# Zocalo-mcp2515.net
KiCad netlist of a schematic drawn in EAGLE
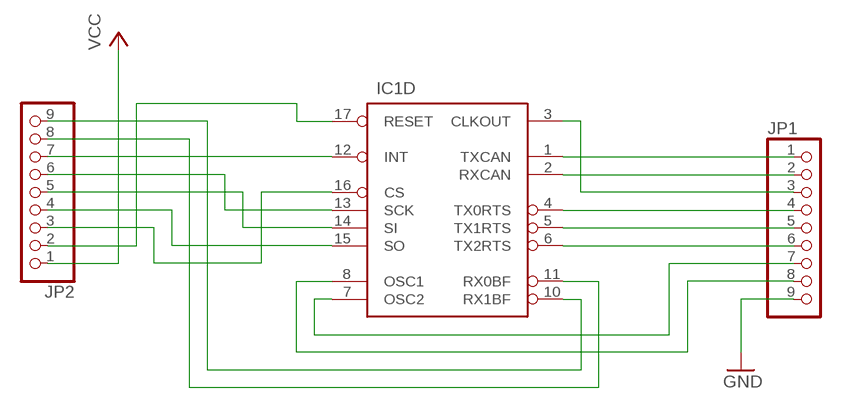
[diagram p0: schematic, sheet 1]

(export (version "E")
  (design (tool "Eeschema 10.0.6"))
  (components
    (comp (ref "IC1")
      (value "MCP2515SO")
      (footprint "eagle-import:SO-18W")
      (libsource (lib "eagle-import") (part "MCP2515SO"))
    )
    (comp (ref "JP1")
      (value "PINHD-1X9")
      (footprint "eagle-import:1X09")
      (libsource (lib "eagle-import") (part "PINHD-1X9"))
    )
    (comp (ref "JP2")
      (value "PINHD-1X9")
      (footprint "eagle-import:1X09")
      (libsource (lib "eagle-import") (part "PINHD-1X9"))
    )
  )
  (nets
    (net (code "1") (name "GND") (class "Default")
      (node (ref "JP1") (pin "9") (pinfunction "9_9") (pintype "passive"))
    )
    (net (code "2") (name "Net-(IC1A-CLKOUT)") (class "Default")
      (node (ref "IC1") (pin "3") (pinfunction "CLKOUT_3") (pintype "output"))
      (node (ref "JP1") (pin "3") (pinfunction "3_3") (pintype "passive"))
    )
    (net (code "3") (name "Net-(IC1A-CS)") (class "Default")
      (node (ref "IC1") (pin "16") (pinfunction "CS_16") (pintype "input"))
      (node (ref "JP2") (pin "3") (pinfunction "3_3") (pintype "passive"))
    )
    (net (code "4") (name "Net-(IC1A-INT)") (class "Default")
      (node (ref "IC1") (pin "12") (pinfunction "INT_12") (pintype "output"))
      (node (ref "JP2") (pin "7") (pinfunction "7_7") (pintype "passive"))
    )
    (net (code "5") (name "Net-(IC1A-OSC1)") (class "Default")
      (node (ref "IC1") (pin "8") (pinfunction "OSC1_8") (pintype "input"))
      (node (ref "JP1") (pin "8") (pinfunction "8_8") (pintype "passive"))
    )
    (net (code "6") (name "Net-(IC1A-OSC2)") (class "Default")
      (node (ref "IC1") (pin "7") (pinfunction "OSC2_7") (pintype "input"))
      (node (ref "JP1") (pin "7") (pinfunction "7_7") (pintype "passive"))
    )
    (net (code "7") (name "Net-(IC1A-RESET)") (class "Default")
      (node (ref "IC1") (pin "17") (pinfunction "RESET_17") (pintype "input"))
      (node (ref "JP2") (pin "2") (pinfunction "2_2") (pintype "passive"))
    )
    (net (code "8") (name "Net-(IC1A-RX0BF)") (class "Default")
      (node (ref "IC1") (pin "11") (pinfunction "RX0BF_11") (pintype "output"))
      (node (ref "JP2") (pin "8") (pinfunction "8_8") (pintype "passive"))
    )
    (net (code "9") (name "Net-(IC1A-RX1BF)") (class "Default")
      (node (ref "IC1") (pin "10") (pinfunction "RX1BF_10") (pintype "output"))
      (node (ref "JP2") (pin "9") (pinfunction "9_9") (pintype "passive"))
    )
    (net (code "10") (name "Net-(IC1A-RXCAN)") (class "Default")
      (node (ref "IC1") (pin "2") (pinfunction "RXCAN_2") (pintype "input"))
      (node (ref "JP1") (pin "2") (pinfunction "2_2") (pintype "passive"))
    )
    (net (code "11") (name "Net-(IC1A-SCK)") (class "Default")
      (node (ref "IC1") (pin "13") (pinfunction "SCK_13") (pintype "input"))
      (node (ref "JP2") (pin "6") (pinfunction "6_6") (pintype "passive"))
    )
    (net (code "12") (name "Net-(IC1A-SI)") (class "Default")
      (node (ref "IC1") (pin "14") (pinfunction "SI_14") (pintype "input"))
      (node (ref "JP2") (pin "5") (pinfunction "5_5") (pintype "passive"))
    )
    (net (code "13") (name "Net-(IC1A-SO)") (class "Default")
      (node (ref "IC1") (pin "15") (pinfunction "SO_15") (pintype "output"))
      (node (ref "JP2") (pin "4") (pinfunction "4_4") (pintype "passive"))
    )
    (net (code "14") (name "Net-(IC1A-TX0RTS)") (class "Default")
      (node (ref "IC1") (pin "4") (pinfunction "TX0RTS_4") (pintype "input"))
      (node (ref "JP1") (pin "4") (pinfunction "4_4") (pintype "passive"))
    )
    (net (code "15") (name "Net-(IC1A-TX1RTS)") (class "Default")
      (node (ref "IC1") (pin "5") (pinfunction "TX1RTS_5") (pintype "input"))
      (node (ref "JP1") (pin "5") (pinfunction "5_5") (pintype "passive"))
    )
    (net (code "16") (name "Net-(IC1A-TX2RTS)") (class "Default")
      (node (ref "IC1") (pin "6") (pinfunction "TX2RTS_6") (pintype "input"))
      (node (ref "JP1") (pin "6") (pinfunction "6_6") (pintype "passive"))
    )
    (net (code "17") (name "Net-(IC1A-TXCAN)") (class "Default")
      (node (ref "IC1") (pin "1") (pinfunction "TXCAN_1") (pintype "output"))
      (node (ref "JP1") (pin "1") (pinfunction "1_1") (pintype "passive"))
    )
    (net (code "18") (name "VCC") (class "Default")
      (node (ref "JP2") (pin "1") (pinfunction "1_1") (pintype "passive"))
    )
  )
)
